# FOC.net
KiCad netlist of a schematic drawn in EasyEDA Pro
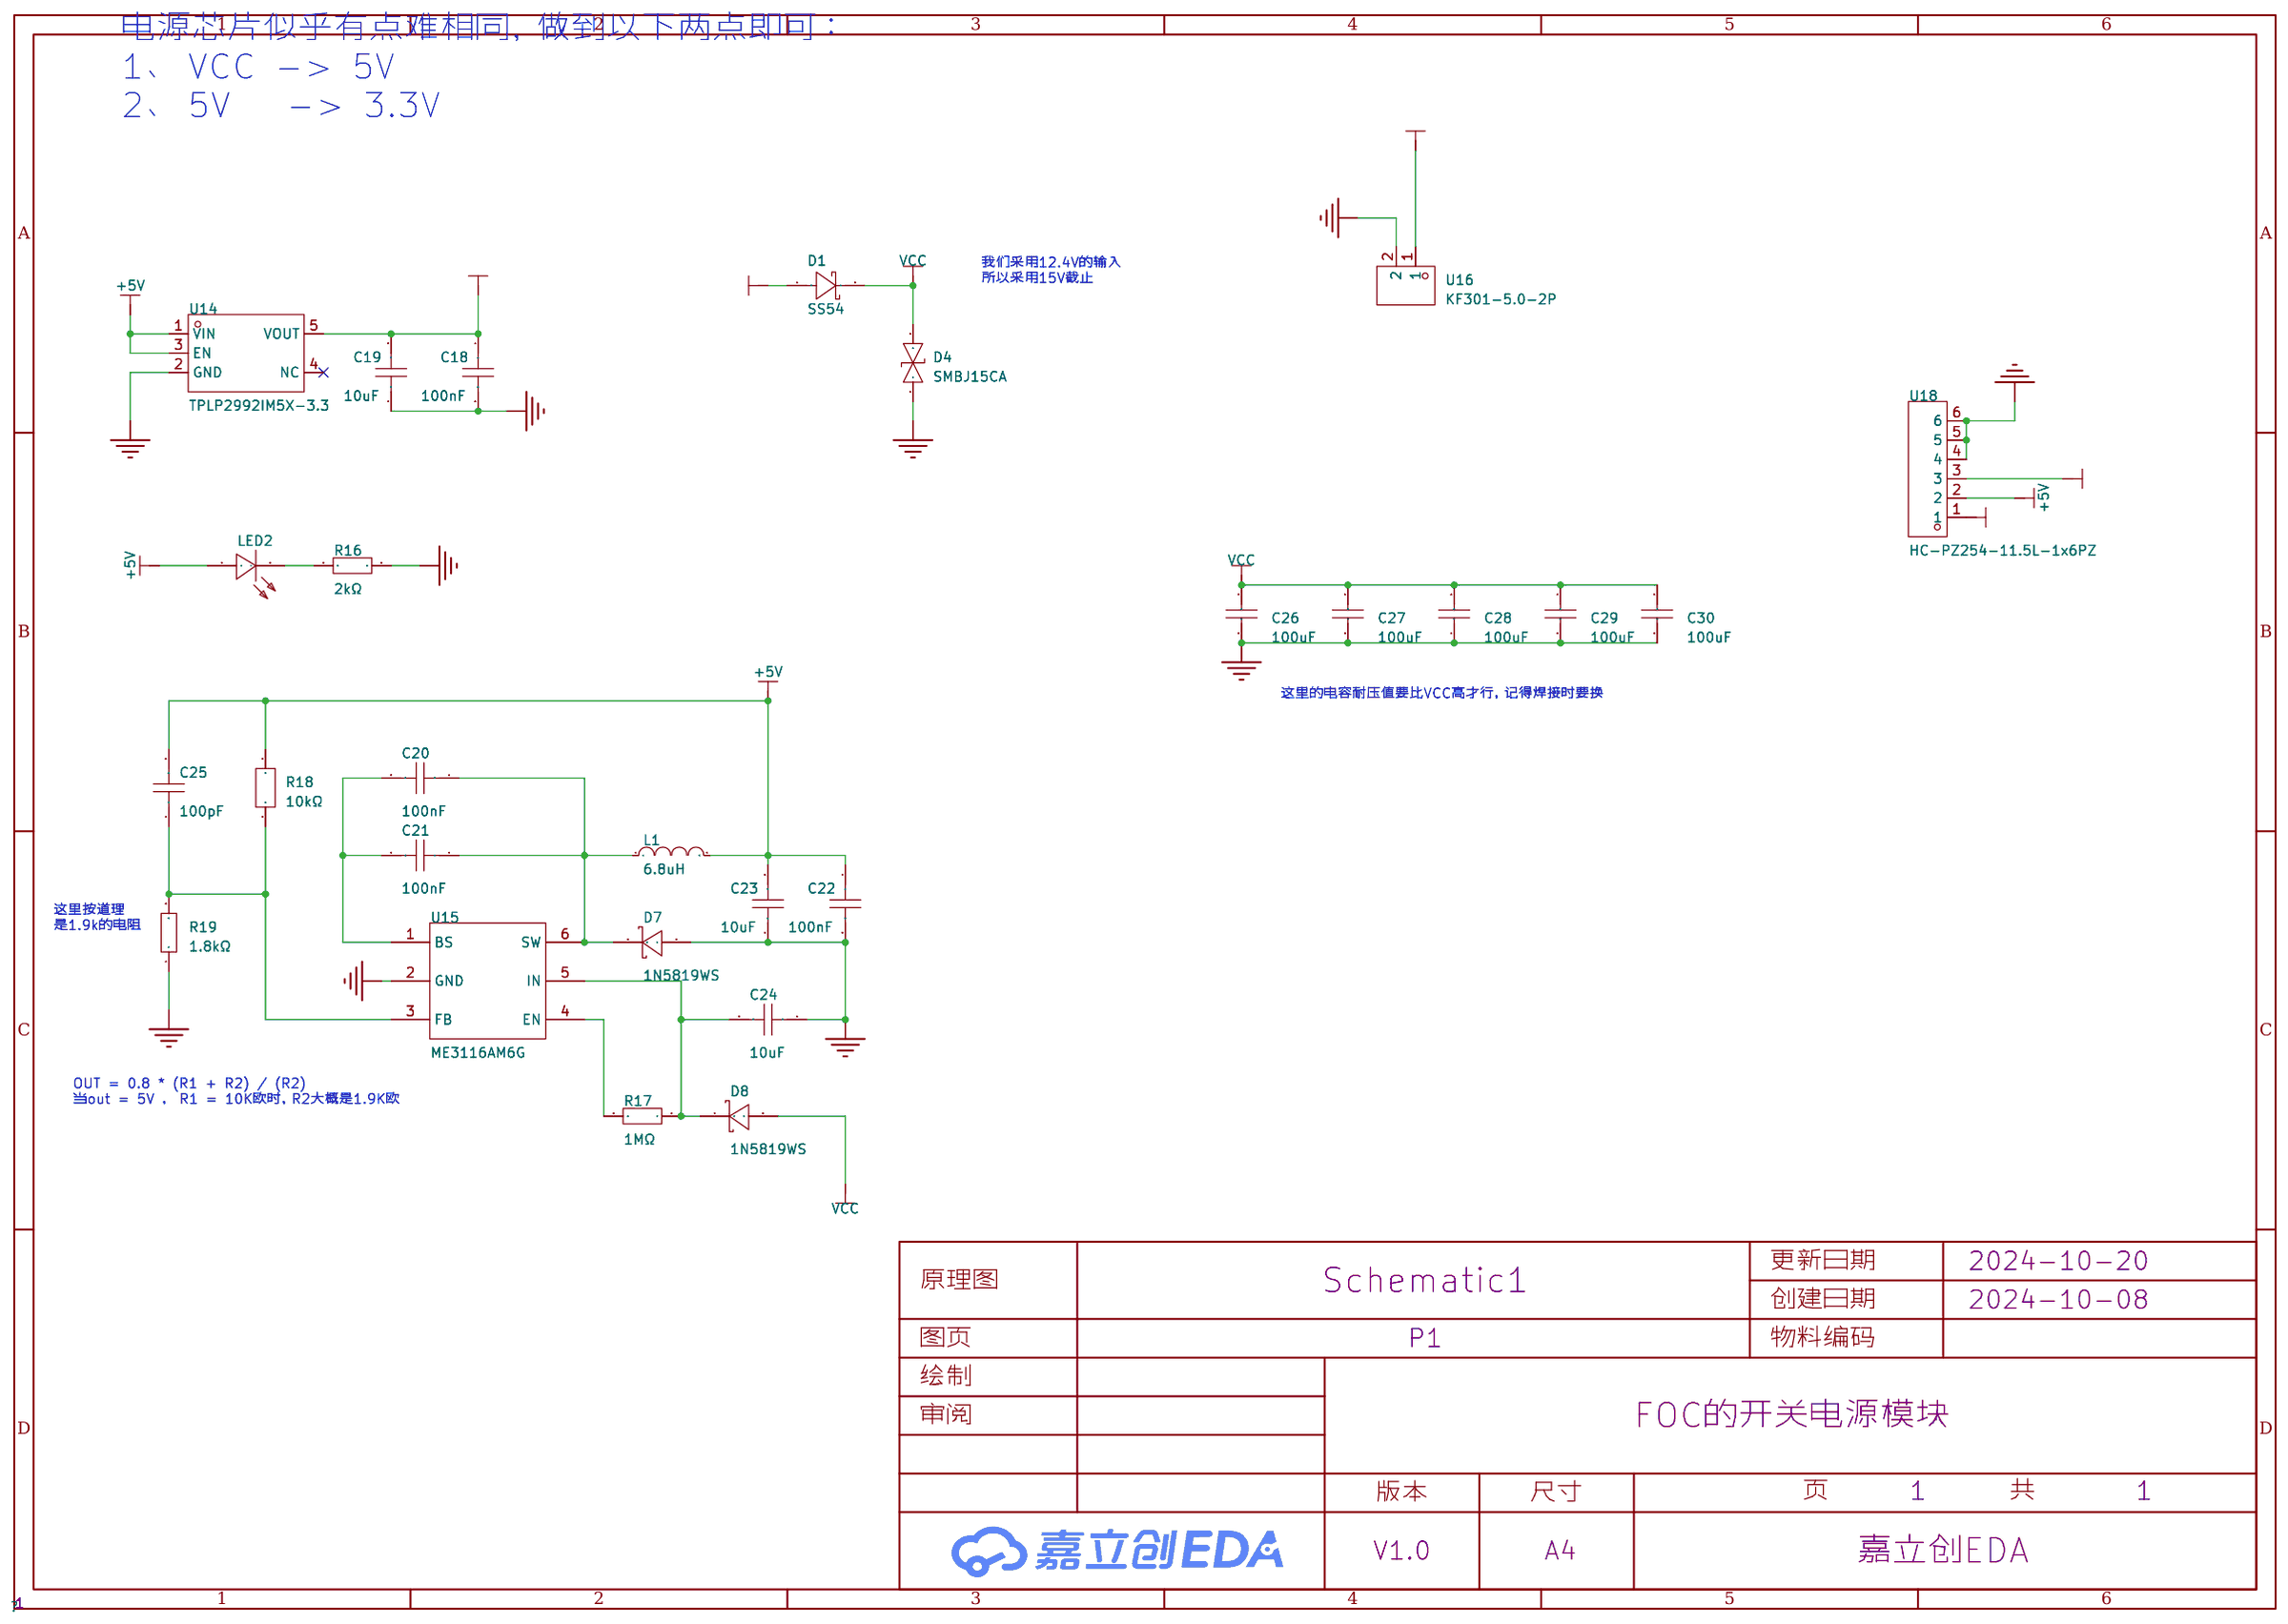
[diagram p0: schematic sheet]

(export (version "E")
  (design (tool "Eeschema 10.0.6"))
  (components
    (comp (ref "C18")
      (value "100nF")
      (footprint "easyedapro:C0603")
      (description "容值:100nF;精度:±10%;额定电压:50V;材质(温度系数):X7R;")
      (fields
        (field (name "Manufacturer Part") "CGA0603X7R104K500JT")
        (field (name "Manufacturer") "HRE(芯声)")
      )
      (libsource (lib "easyedapro") (part "CGA0603X7R104K500JT"))
    )
    (comp (ref "C19")
      (value "10uF")
      (footprint "easyedapro:C0603")
      (description "容值:10uF;精度:±20%;额定电压:35V;材质(温度系数):X5R;")
      (fields
        (field (name "Manufacturer Part") "GRM188R6YA106MA73D")
        (field (name "Manufacturer") "muRata(村田)")
      )
      (libsource (lib "easyedapro") (part "GRM188R6YA106MA73D"))
    )
    (comp (ref "C20")
      (value "100nF")
      (footprint "easyedapro:C0603")
      (description "容值:100nF;精度:±10%;额定电压:50V;材质(温度系数):X7R;")
      (fields
        (field (name "Manufacturer Part") "CGA0603X7R104K500JT")
        (field (name "Manufacturer") "HRE(芯声)")
      )
      (libsource (lib "easyedapro") (part "CGA0603X7R104K500JT"))
    )
    (comp (ref "C21")
      (value "100nF")
      (footprint "easyedapro:C0603")
      (description "容值:100nF;精度:±10%;额定电压:50V;材质(温度系数):X7R;")
      (fields
        (field (name "Manufacturer Part") "CGA0603X7R104K500JT")
        (field (name "Manufacturer") "HRE(芯声)")
      )
      (libsource (lib "easyedapro") (part "CGA0603X7R104K500JT"))
    )
    (comp (ref "C22")
      (value "100nF")
      (footprint "easyedapro:C0603")
      (description "容值:100nF;精度:±10%;额定电压:50V;材质(温度系数):X7R;")
      (fields
        (field (name "Manufacturer Part") "CGA0603X7R104K500JT")
        (field (name "Manufacturer") "HRE(芯声)")
      )
      (libsource (lib "easyedapro") (part "CGA0603X7R104K500JT"))
    )
    (comp (ref "C23")
      (value "10uF")
      (footprint "easyedapro:C0603")
      (description "容值:10uF;精度:±20%;额定电压:35V;材质(温度系数):X5R;")
      (fields
        (field (name "Manufacturer Part") "GRM188R6YA106MA73D")
        (field (name "Manufacturer") "muRata(村田)")
      )
      (libsource (lib "easyedapro") (part "GRM188R6YA106MA73D"))
    )
    (comp (ref "C24")
      (value "10uF")
      (footprint "easyedapro:C0603")
      (description "容值:10uF;精度:±20%;额定电压:35V;材质(温度系数):X5R;")
      (fields
        (field (name "Manufacturer Part") "GRM188R6YA106MA73D")
        (field (name "Manufacturer") "muRata(村田)")
      )
      (libsource (lib "easyedapro") (part "GRM188R6YA106MA73D"))
    )
    (comp (ref "C25")
      (value "100pF")
      (footprint "easyedapro:C0603")
      (description "容值:100pF;精度:±5%;额定电压:50V;材质(温度系数):NP0;")
      (fields
        (field (name "Manufacturer Part") "CC0603JRNPO9BN101")
        (field (name "Manufacturer") "YAGEO(国巨)")
      )
      (libsource (lib "easyedapro") (part "CC0603JRNPO9BN101"))
    )
    (comp (ref "C26")
      (value "100uF")
      (footprint "easyedapro:C1206")
      (description "容值:100uF;精度:±20%;额定电压:10V;材质(温度系数):X5R;")
      (fields (field (name "Manufacturer Part") "C3216X5R1A107MT0A0E") (field (name "Manufacturer") "TDK"))
      (libsource (lib "easyedapro") (part "C3216X5R1A107MT0A0E"))
    )
    (comp (ref "C27")
      (value "100uF")
      (footprint "easyedapro:C1206")
      (description "容值:100uF;精度:±20%;额定电压:10V;材质(温度系数):X5R;")
      (fields (field (name "Manufacturer Part") "C3216X5R1A107MT0A0E") (field (name "Manufacturer") "TDK"))
      (libsource (lib "easyedapro") (part "C3216X5R1A107MT0A0E"))
    )
    (comp (ref "C28")
      (value "100uF")
      (footprint "easyedapro:C1206")
      (description "容值:100uF;精度:±20%;额定电压:10V;材质(温度系数):X5R;")
      (fields (field (name "Manufacturer Part") "C3216X5R1A107MT0A0E") (field (name "Manufacturer") "TDK"))
      (libsource (lib "easyedapro") (part "C3216X5R1A107MT0A0E"))
    )
    (comp (ref "C29")
      (value "100uF")
      (footprint "easyedapro:C1206")
      (description "容值:100uF;精度:±20%;额定电压:10V;材质(温度系数):X5R;")
      (fields (field (name "Manufacturer Part") "C3216X5R1A107MT0A0E") (field (name "Manufacturer") "TDK"))
      (libsource (lib "easyedapro") (part "C3216X5R1A107MT0A0E"))
    )
    (comp (ref "C30")
      (value "100uF")
      (footprint "easyedapro:C1206")
      (description "容值:100uF;精度:±20%;额定电压:10V;材质(温度系数):X5R;")
      (fields (field (name "Manufacturer Part") "C3216X5R1A107MT0A0E") (field (name "Manufacturer") "TDK"))
      (libsource (lib "easyedapro") (part "C3216X5R1A107MT0A0E"))
    )
    (comp (ref "D1")
      (value "SS54")
      (footprint "easyedapro:SMA_L4.3-W2.6-LS5.0-FD")
      (description "二极管配置:独立式;正向压降(Vf):550mV@5.0A;直流反向耐压(Vr):40V;整流电流:5A;")
      (fields (field (name "Manufacturer") "宏迦橙"))
      (libsource (lib "easyedapro") (part "SS54_C7420369"))
    )
    (comp (ref "D4")
      (value "SMBJ15CA")
      (footprint "easyedapro:SMB_L4.6-W3.6-LS5.3-BI")
      (description "极性:单向;反向截止电压(Vrwm):15V;最大钳位电压:24.4V;峰值脉冲电流(Ipp)@10/1000us:24A;击穿电压:16.7V;")
      (fields (field (name "Manufacturer") "MDD"))
      (libsource (lib "easyedapro") (part "SMBJ15CA-C113989"))
    )
    (comp (ref "D7")
      (value "1N5819WS")
      (footprint "easyedapro:SOD-323_L1.8-W1.3-LS2.5-RD")
      (description "正向压降(Vf):600mV@1A;直流反向耐压(Vr):40V;平均整流电流(Io):1A;")
      (fields (field (name "Manufacturer") "Hottech(合科泰)"))
      (libsource (lib "easyedapro") (part "1N5819WS"))
    )
    (comp (ref "D8")
      (value "1N5819WS")
      (footprint "easyedapro:SOD-323_L1.8-W1.3-LS2.5-RD")
      (description "正向压降(Vf):600mV@1A;直流反向耐压(Vr):40V;平均整流电流(Io):1A;")
      (fields (field (name "Manufacturer") "Hottech(合科泰)"))
      (libsource (lib "easyedapro") (part "1N5819WS"))
    )
    (comp (ref "L1")
      (value "6.8uH")
      (footprint "easyedapro:IND-SMD_L3.2-W2.5_L3225")
      (description "电感值:6.8uH;精度:±10%;额定电流:450mA;饱和电流(Isat):-;直流电阻(DCR):600mΩ;")
      (fields (field (name "Manufacturer Part") "CMI322513X6R8KT") (field (name "Manufacturer") "FH(风华)"))
      (libsource (lib "easyedapro") (part "CMI322513X6R8KT"))
    )
    (comp (ref "LED2")
      (value "SZYY0805G")
      (footprint "easyedapro:LED0805-R-RD")
      (description "发光颜色:翠绿色;")
      (fields (field (name "Manufacturer") "yongyu(永裕光电)"))
      (libsource (lib "easyedapro") (part "SZYY0805G"))
    )
    (comp (ref "R16")
      (value "2kΩ")
      (footprint "easyedapro:R0603")
      (description "电阻类型:厚膜电阻;阻值:2kΩ;精度:±1%;功率:100mW;最大工作电压:75V;温度系数:±100ppm/°C;")
      (fields
        (field (name "Manufacturer Part") "0603WAF2001T5E")
        (field (name "Manufacturer") "UNI-ROYAL(厚声)")
      )
      (libsource (lib "easyedapro") (part "0603WAF2001T5E"))
    )
    (comp (ref "R17")
      (value "1MΩ")
      (footprint "easyedapro:R0603")
      (description "电阻类型:厚膜电阻;阻值:1MΩ;精度:±1%;功率:100mW;最大工作电压:75V;温度系数:±100ppm/°C;")
      (fields
        (field (name "Manufacturer Part") "0603WAF1004T5E")
        (field (name "Manufacturer") "UNI-ROYAL(厚声)")
      )
      (libsource (lib "easyedapro") (part "0603WAF1004T5E"))
    )
    (comp (ref "R18")
      (value "10kΩ")
      (footprint "easyedapro:R0603")
      (description "电阻类型:厚膜电阻;阻值:10kΩ;精度:±5%;功率:100mW;最大工作电压:75V;温度系数:±100ppm/°C;")
      (fields (field (name "Manufacturer Part") "FRC0603J103TS") (field (name "Manufacturer") "FOJAN(富捷)"))
      (libsource (lib "easyedapro") (part "FRC0603J103TS"))
    )
    (comp (ref "R19")
      (value "1.8kΩ")
      (footprint "easyedapro:R0603")
      (description "电阻类型:厚膜电阻;阻值:1.8kΩ;精度:±1%;功率:100mW;最大工作电压:75V;温度系数:±100ppm/°C;")
      (fields
        (field (name "Manufacturer Part") "0603WAF1801T5E")
        (field (name "Manufacturer") "UNI-ROYAL(厚声)")
      )
      (libsource (lib "easyedapro") (part "0603WAF1801T5E"))
    )
    (comp (ref "U14")
      (value "TPLP2992IM5X-3.3")
      (footprint "easyedapro:SOT-23-5_L2.9-W1.6-P0.95-LS2.8-BL")
      (fields (field (name "Manufacturer") "TECH PUBLIC(台舟)"))
      (libsource (lib "easyedapro") (part "TPLP2992IM5X-3.3"))
    )
    (comp (ref "U15")
      (value "ME3116AM6G")
      (footprint "easyedapro:SOT-23-6_L2.9-W1.6-P0.95-LS2.8-BL")
      (description "功能类型:降压型;输入电压:-;输出电流(最大值):-;")
      (fields (field (name "Manufacturer") "MICRONE(南京微盟)"))
      (libsource (lib "easyedapro") (part "ME3116"))
    )
    (comp (ref "U16")
      (value "KF301-5.0-2P")
      (footprint "easyedapro:CONN-TH_P5.00_KF301-5.0-2P")
      (fields (field (name "Manufacturer") "KEFA(科发)"))
      (libsource (lib "easyedapro") (part "KF301-5.0-2P"))
    )
    (comp (ref "U18")
      (value "HC-PZ254-11.5L-1x6PZ")
      (footprint "easyedapro:hdr-th_6p-p2.54-v-f")
      (fields (field (name "Manufacturer") "HC(虹成电子)"))
      (libsource (lib "easyedapro") (part "hc-pz254-11.5l-1x6pz"))
    )
  )
  (nets
    (net (code "1") (name "+5V") (class "Default")
      (node (ref "C22") (pin "1") (pinfunction "1_1") (pintype "unspecified"))
      (node (ref "C23") (pin "2") (pinfunction "2_2") (pintype "input"))
      (node (ref "C25") (pin "2") (pinfunction "2_2") (pintype "unspecified"))
      (node (ref "L1") (pin "2") (pinfunction "2_2") (pintype "unspecified"))
      (node (ref "LED2") (pin "1") (pinfunction "+_1") (pintype "unspecified"))
      (node (ref "R18") (pin "2") (pinfunction "2_2") (pintype "unspecified"))
      (node (ref "U14") (pin "1") (pinfunction "VIN_1") (pintype "input"))
      (node (ref "U14") (pin "3") (pinfunction "EN_3") (pintype "input"))
      (node (ref "U18") (pin "2") (pinfunction "2_2") (pintype "unspecified"))
    )
    (net (code "2") (name "3V3") (class "Default")
      (node (ref "C18") (pin "1") (pinfunction "1_1") (pintype "unspecified"))
      (node (ref "C19") (pin "2") (pinfunction "2_2") (pintype "input"))
      (node (ref "U14") (pin "5") (pinfunction "VOUT_5") (pintype "input"))
      (node (ref "U18") (pin "3") (pinfunction "3_3") (pintype "unspecified"))
    )
    (net (code "3") (name "GND") (class "Default")
      (node (ref "C18") (pin "2") (pinfunction "2_2") (pintype "unspecified"))
      (node (ref "C19") (pin "1") (pinfunction "1_1") (pintype "input"))
      (node (ref "C22") (pin "2") (pinfunction "2_2") (pintype "unspecified"))
      (node (ref "C23") (pin "1") (pinfunction "1_1") (pintype "input"))
      (node (ref "C24") (pin "1") (pinfunction "1_1") (pintype "input"))
      (node (ref "C26") (pin "1") (pinfunction "1_1") (pintype "input"))
      (node (ref "C27") (pin "1") (pinfunction "1_1") (pintype "input"))
      (node (ref "C28") (pin "1") (pinfunction "1_1") (pintype "input"))
      (node (ref "C29") (pin "1") (pinfunction "1_1") (pintype "input"))
      (node (ref "C30") (pin "1") (pinfunction "1_1") (pintype "input"))
      (node (ref "D4") (pin "1") (pinfunction "1_1") (pintype "unspecified"))
      (node (ref "D7") (pin "2") (pinfunction "A_2") (pintype "unspecified"))
      (node (ref "R16") (pin "2") (pinfunction "2_2") (pintype "input"))
      (node (ref "R19") (pin "1") (pinfunction "1_1") (pintype "input"))
      (node (ref "U14") (pin "2") (pinfunction "GND_2") (pintype "input"))
      (node (ref "U15") (pin "2") (pinfunction "GND_2") (pintype "unspecified"))
      (node (ref "U16") (pin "2") (pinfunction "2_2") (pintype "unspecified"))
      (node (ref "U18") (pin "4") (pinfunction "4_4") (pintype "unspecified"))
      (node (ref "U18") (pin "5") (pinfunction "5_5") (pintype "unspecified"))
      (node (ref "U18") (pin "6") (pinfunction "6_6") (pintype "unspecified"))
    )
    (net (code "4") (name "Net-(D7-K)") (class "Default")
      (node (ref "C20") (pin "1") (pinfunction "1_1") (pintype "unspecified"))
      (node (ref "C21") (pin "1") (pinfunction "1_1") (pintype "unspecified"))
      (node (ref "D7") (pin "1") (pinfunction "K_1") (pintype "unspecified"))
      (node (ref "L1") (pin "1") (pinfunction "1_1") (pintype "unspecified"))
      (node (ref "U15") (pin "6") (pinfunction "SW_6") (pintype "unspecified"))
    )
    (net (code "5") (name "Net-(D8-K)") (class "Default")
      (node (ref "C24") (pin "2") (pinfunction "2_2") (pintype "input"))
      (node (ref "D8") (pin "1") (pinfunction "K_1") (pintype "unspecified"))
      (node (ref "R17") (pin "1") (pinfunction "1_1") (pintype "input"))
      (node (ref "U15") (pin "5") (pinfunction "IN_5") (pintype "unspecified"))
    )
    (net (code "6") (name "Net-(LED2--)") (class "Default")
      (node (ref "LED2") (pin "2") (pinfunction "-_2") (pintype "unspecified"))
      (node (ref "R16") (pin "1") (pinfunction "1_1") (pintype "input"))
    )
    (net (code "7") (name "Net-(U15-BS)") (class "Default")
      (node (ref "C20") (pin "2") (pinfunction "2_2") (pintype "unspecified"))
      (node (ref "C21") (pin "2") (pinfunction "2_2") (pintype "unspecified"))
      (node (ref "U15") (pin "1") (pinfunction "BS_1") (pintype "unspecified"))
    )
    (net (code "8") (name "Net-(U15-EN)") (class "Default")
      (node (ref "R17") (pin "2") (pinfunction "2_2") (pintype "input"))
      (node (ref "U15") (pin "4") (pinfunction "EN_4") (pintype "unspecified"))
    )
    (net (code "9") (name "Net-(U15-FB)") (class "Default")
      (node (ref "C25") (pin "1") (pinfunction "1_1") (pintype "unspecified"))
      (node (ref "R18") (pin "1") (pinfunction "1_1") (pintype "unspecified"))
      (node (ref "R19") (pin "2") (pinfunction "2_2") (pintype "input"))
      (node (ref "U15") (pin "3") (pinfunction "FB_3") (pintype "unspecified"))
    )
    (net (code "10") (name "VCC") (class "Default")
      (node (ref "C26") (pin "2") (pinfunction "2_2") (pintype "input"))
      (node (ref "C27") (pin "2") (pinfunction "2_2") (pintype "input"))
      (node (ref "C28") (pin "2") (pinfunction "2_2") (pintype "input"))
      (node (ref "C29") (pin "2") (pinfunction "2_2") (pintype "input"))
      (node (ref "C30") (pin "2") (pinfunction "2_2") (pintype "input"))
      (node (ref "D1") (pin "2") (pinfunction "K_2") (pintype "unspecified"))
      (node (ref "D4") (pin "2") (pinfunction "2_2") (pintype "unspecified"))
      (node (ref "D8") (pin "2") (pinfunction "A_2") (pintype "unspecified"))
      (node (ref "U18") (pin "1") (pinfunction "1_1") (pintype "unspecified"))
    )
    (net (code "11") (name "VCC_IN") (class "Default")
      (node (ref "D1") (pin "1") (pinfunction "A_1") (pintype "unspecified"))
      (node (ref "U16") (pin "1") (pinfunction "1_1") (pintype "unspecified"))
    )
    (net (code "12") (name "unconnected-(U14-NC-Pad4)") (class "Default")
      (node (ref "U14") (pin "4") (pinfunction "NC_4") (pintype "input+no_connect"))
    )
  )
)
